# LED_and_LCD.net
KiCad netlist of a schematic drawn in Altium Designer
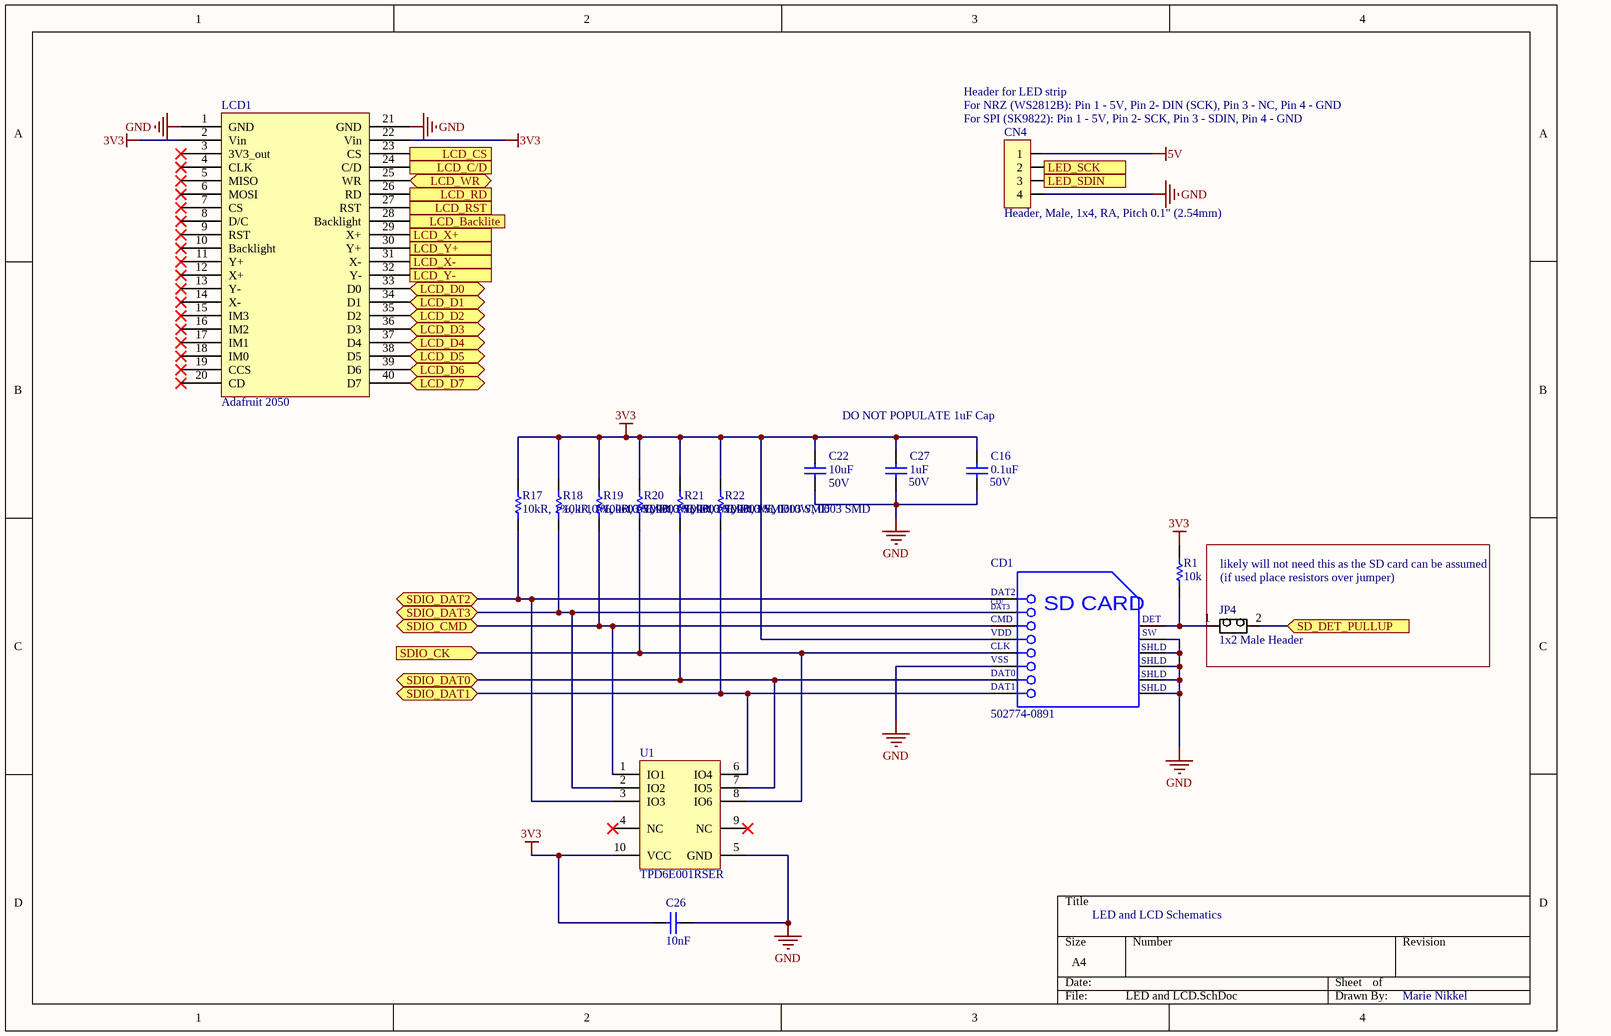
[diagram p0: LED and LCD.SchDoc]

(export (version "E")
  (design (tool "Eeschema 10.0.6"))
  (components
    (comp (ref "C16")
      (value "CL10B104JB8NNNC")
      (footprint "FP-CL10-0_1-IPC_A")
      (description "CAP CER 0.1UF 50V X7R 0603")
      (fields
        (field (name "TOLERANCE") "5%")
        (field (name "VOLTAGE") "50V")
        (field (name "CAPACITANCE") "0.1uF")
      )
      (libsource (lib "AUVIC") (part "CAP-NP-2"))
    )
    (comp (ref "C22")
      (value "CL31B106KBHNNNE")
      (footprint "CAPC3216X180X50ML20T30")
      (description "Cap Ceramic 10uF 50V X7R 10% Pad SMD 1206 125°C T/R")
      (fields
        (field (name "VOLTAGE RATING (DC)") "50V")
        (field (name "CAPACITANCE") "10uF")
        (field (name "TOLERANCE") "10%")
      )
      (libsource (lib "AUVIC") (part "CAP-NP-2"))
    )
    (comp (ref "C26")
      (value "10nF")
      (footprint "CAPC1608N(0603\")")
      (description "Capacitor, Ceramic, 50V, +/- 10%, 0603 SMD")
      (fields
        (field (name "MFG") "Samsung")
        (field (name "Comment") "10 nF, 50V 0603 SMD, Ceramic")
        (field (name "CREATED BY") "Gabriel")
        (field (name "PUBLISHER") "AUVic")
      )
      (libsource (lib "") (part "Symbol_1"))
    )
    (comp (ref "C27")
      (value "CL21B105KBFNNNG")
      (footprint "0803 CAP")
      (description "SAMSUNG ELECTRO-MECHANICS - CL21B105KBFNNNG - MLCC CAPACITORS")
      (fields
        (field (name "CAPACITANCE") "1uF")
        (field (name "TOLERANCE") "10%")
        (field (name "VOLTAGE") "50V")
      )
      (libsource (lib "") (part "Symbol_3"))
    )
    (comp (ref "CD1")
      (value "502774-0891")
      (footprint "MOLX-502774-0891_V")
      (description "Micro SD Memory Card Connector, 0.5 A, 10 V (DC), -25 to 85 degC, 8-Pin SMT, RoHS, Tape and Reel")
      (fields (field (name "MANUFACTURER") "Molex"))
      (libsource (lib "Altium Content Vault") (part "CN-SD-8-2SW-4S_B"))
    )
    (comp (ref "CN4")
      (value "Header, Male, 1x4, RA, Pitch 0.1\" (2.54mm)")
      (footprint "HEADER, MALE, SHROUDED, 4x1, PITCH 0.1\" (2.54mm), RA")
      (description "Connector Header Through Hole, Right Angle 4 position 0.100\" (2.54mm)")
      (fields (field (name "CREATED BY") "Miguel Manguerra"))
      (libsource (lib "") (part "Symbol_2"))
    )
    (comp (ref "JP4")
      (value "1x2 Male Header")
      (footprint "2X1 Males Header")
      (fields (field (name "MADE BY") "Andy Bates"))
      (libsource (lib "AUVIC") (part "1x2 Male Header"))
    )
    (comp (ref "LCD1")
      (value "Adafruit 2050")
      (footprint "LCD_touchscreen_tft")
      (description "3.5\" TFT 320X480 TOUCHSCREEN")
      (libsource (lib "AUVIC") (part "Adafruit 2050"))
    )
    (comp (ref "R1")
      (value "10k")
      (footprint "RESC1608N(0603\")")
      (description "10kR, 1%, 1/10W, 0603 SMD")
      (fields (field (name "MADE BY") "Ashwin Sira"))
      (libsource (lib "AUVIC") (part "Symbol"))
    )
    (comp (ref "R17")
      (value "10kR, 1%, 1/10W, 0603 SMD")
      (footprint "RESC1608N(0603\")")
      (fields (field (name "MADE BY") "Ashwin Sira"))
      (libsource (lib "AUVIC") (part "Symbol"))
    )
    (comp (ref "R18")
      (value "10kR, 1%, 1/10W, 0603 SMD")
      (footprint "RESC1608N(0603\")")
      (fields (field (name "MADE BY") "Ashwin Sira"))
      (libsource (lib "AUVIC") (part "Symbol"))
    )
    (comp (ref "R19")
      (value "10kR, 1%, 1/10W, 0603 SMD")
      (footprint "RESC1608N(0603\")")
      (fields (field (name "MADE BY") "Ashwin Sira"))
      (libsource (lib "AUVIC") (part "Symbol"))
    )
    (comp (ref "R20")
      (value "10kR, 1%, 1/10W, 0603 SMD")
      (footprint "RESC1608N(0603\")")
      (fields (field (name "MADE BY") "Ashwin Sira"))
      (libsource (lib "AUVIC") (part "Symbol"))
    )
    (comp (ref "R21")
      (value "10kR, 1%, 1/10W, 0603 SMD")
      (footprint "RESC1608N(0603\")")
      (fields (field (name "MADE BY") "Ashwin Sira"))
      (libsource (lib "AUVIC") (part "Symbol"))
    )
    (comp (ref "R22")
      (value "10kR, 1%, 1/10W, 0603 SMD")
      (footprint "RESC1608N(0603\")")
      (fields (field (name "MADE BY") "Ashwin Sira"))
      (libsource (lib "AUVIC") (part "Symbol"))
    )
    (comp (ref "U1")
      (value "TPD6E001RSER")
      (footprint "RSE0010A_V")
      (fields (field (name "MANUFACTURER") "Texas Instruments"))
      (libsource (lib "Altium Content Vault") (part "TI-TPD6E001-UQFN_RSE-10"))
    )
  )
  (nets
    (net (code "1") (name "/LCD_Backlite") (class "Default")
      (node (ref "LCD1") (pin "28") (pinfunction "Backlight_28") (pintype "passive"))
    )
    (net (code "2") (name "/LCD_CS") (class "Default")
      (node (ref "LCD1") (pin "23") (pinfunction "CS_23") (pintype "passive"))
    )
    (net (code "3") (name "/LCD_C{slash}D") (class "Default")
      (node (ref "LCD1") (pin "24") (pinfunction "C/D_24") (pintype "passive"))
    )
    (net (code "4") (name "/LCD_D0") (class "Default")
      (node (ref "LCD1") (pin "33") (pinfunction "D0_33") (pintype "passive"))
    )
    (net (code "5") (name "/LCD_D1") (class "Default")
      (node (ref "LCD1") (pin "34") (pinfunction "D1_34") (pintype "passive"))
    )
    (net (code "6") (name "/LCD_D2") (class "Default")
      (node (ref "LCD1") (pin "35") (pinfunction "D2_35") (pintype "passive"))
    )
    (net (code "7") (name "/LCD_D3") (class "Default")
      (node (ref "LCD1") (pin "36") (pinfunction "D3_36") (pintype "passive"))
    )
    (net (code "8") (name "/LCD_D4") (class "Default")
      (node (ref "LCD1") (pin "37") (pinfunction "D4_37") (pintype "passive"))
    )
    (net (code "9") (name "/LCD_D5") (class "Default")
      (node (ref "LCD1") (pin "38") (pinfunction "D5_38") (pintype "passive"))
    )
    (net (code "10") (name "/LCD_D6") (class "Default")
      (node (ref "LCD1") (pin "39") (pinfunction "D6_39") (pintype "passive"))
    )
    (net (code "11") (name "/LCD_D7") (class "Default")
      (node (ref "LCD1") (pin "40") (pinfunction "D7_40") (pintype "passive"))
    )
    (net (code "12") (name "/LCD_RD") (class "Default")
      (node (ref "LCD1") (pin "26") (pinfunction "RD_26") (pintype "passive"))
    )
    (net (code "13") (name "/LCD_RST") (class "Default")
      (node (ref "LCD1") (pin "27") (pinfunction "RST_27") (pintype "passive"))
    )
    (net (code "14") (name "/LCD_WR") (class "Default")
      (node (ref "LCD1") (pin "25") (pinfunction "WR_25") (pintype "passive"))
    )
    (net (code "15") (name "/LCD_X+") (class "Default")
      (node (ref "LCD1") (pin "29") (pinfunction "X+_29") (pintype "passive"))
    )
    (net (code "16") (name "/LCD_X-") (class "Default")
      (node (ref "LCD1") (pin "31") (pinfunction "X-_31") (pintype "passive"))
    )
    (net (code "17") (name "/LCD_Y+") (class "Default")
      (node (ref "LCD1") (pin "30") (pinfunction "Y+_30") (pintype "passive"))
    )
    (net (code "18") (name "/LCD_Y-") (class "Default")
      (node (ref "LCD1") (pin "32") (pinfunction "Y-_32") (pintype "passive"))
    )
    (net (code "19") (name "/LED_SCK") (class "Default")
      (node (ref "CN4") (pin "2") (pinfunction "2_2") (pintype "passive"))
    )
    (net (code "20") (name "/LED_SDIN") (class "Default")
      (node (ref "CN4") (pin "3") (pinfunction "3_3") (pintype "passive"))
    )
    (net (code "21") (name "/SDIO_CK") (class "Default")
      (node (ref "CD1") (pin "5") (pinfunction "CLK_5") (pintype "passive"))
      (node (ref "R20") (pin "1") (pinfunction "1_1") (pintype "passive"))
      (node (ref "U1") (pin "8") (pinfunction "IO6_8") (pintype "passive"))
    )
    (net (code "22") (name "/SDIO_CMD") (class "Default")
      (node (ref "CD1") (pin "3") (pinfunction "CMD_3") (pintype "passive"))
      (node (ref "R19") (pin "1") (pinfunction "1_1") (pintype "passive"))
      (node (ref "U1") (pin "1") (pinfunction "IO1_1") (pintype "passive"))
    )
    (net (code "23") (name "/SDIO_DAT0") (class "Default")
      (node (ref "CD1") (pin "7") (pinfunction "DAT0_7") (pintype "passive"))
      (node (ref "R21") (pin "1") (pinfunction "1_1") (pintype "passive"))
      (node (ref "U1") (pin "7") (pinfunction "IO5_7") (pintype "passive"))
    )
    (net (code "24") (name "/SDIO_DAT1") (class "Default")
      (node (ref "CD1") (pin "8") (pinfunction "DAT1_8") (pintype "passive"))
      (node (ref "R22") (pin "1") (pinfunction "1_1") (pintype "passive"))
      (node (ref "U1") (pin "6") (pinfunction "IO4_6") (pintype "passive"))
    )
    (net (code "25") (name "/SDIO_DAT2") (class "Default")
      (node (ref "CD1") (pin "1") (pinfunction "DAT2_1") (pintype "passive"))
      (node (ref "R17") (pin "1") (pinfunction "1_1") (pintype "passive"))
      (node (ref "U1") (pin "3") (pinfunction "IO3_3") (pintype "passive"))
    )
    (net (code "26") (name "/SDIO_DAT3") (class "Default")
      (node (ref "CD1") (pin "2") (pinfunction "CD/DAT3_2") (pintype "passive"))
      (node (ref "R18") (pin "1") (pinfunction "1_1") (pintype "passive"))
      (node (ref "U1") (pin "2") (pinfunction "IO2_2") (pintype "passive"))
    )
    (net (code "27") (name "/SD_DET_PULLUP") (class "Default")
      (node (ref "JP4") (pin "2") (pinfunction "2_2") (pintype "passive"))
    )
    (net (code "28") (name "3V3") (class "Default")
      (node (ref "C16") (pin "2") (pinfunction "2_2") (pintype "passive"))
      (node (ref "C22") (pin "2") (pinfunction "2_2") (pintype "passive"))
      (node (ref "C26") (pin "1") (pinfunction "Anode_1") (pintype "passive"))
      (node (ref "C27") (pin "2") (pinfunction "2_2") (pintype "passive"))
      (node (ref "CD1") (pin "4") (pinfunction "VDD_4") (pintype "passive"))
      (node (ref "LCD1") (pin "2") (pinfunction "Vin_2") (pintype "passive"))
      (node (ref "LCD1") (pin "22") (pinfunction "Vin_22") (pintype "passive"))
      (node (ref "R1") (pin "2") (pinfunction "2_2") (pintype "passive"))
      (node (ref "R17") (pin "2") (pinfunction "2_2") (pintype "passive"))
      (node (ref "R18") (pin "2") (pinfunction "2_2") (pintype "passive"))
      (node (ref "R19") (pin "2") (pinfunction "2_2") (pintype "passive"))
      (node (ref "R20") (pin "2") (pinfunction "2_2") (pintype "passive"))
      (node (ref "R21") (pin "2") (pinfunction "2_2") (pintype "passive"))
      (node (ref "R22") (pin "2") (pinfunction "2_2") (pintype "passive"))
      (node (ref "U1") (pin "10") (pinfunction "VCC_10") (pintype "power_in"))
    )
    (net (code "29") (name "5V") (class "Default")
      (node (ref "CN4") (pin "1") (pinfunction "1_1") (pintype "passive"))
    )
    (net (code "30") (name "GND") (class "Default")
      (node (ref "C16") (pin "1") (pinfunction "1_1") (pintype "passive"))
      (node (ref "C22") (pin "1") (pinfunction "1_1") (pintype "passive"))
      (node (ref "C26") (pin "2") (pinfunction "Cathode_2") (pintype "passive"))
      (node (ref "C27") (pin "1") (pinfunction "1_1") (pintype "passive"))
      (node (ref "CD1") (pin "10") (pinfunction "SWITCH_10") (pintype "passive"))
      (node (ref "CD1") (pin "11") (pinfunction "SHLD_11") (pintype "passive"))
      (node (ref "CD1") (pin "12") (pinfunction "SHLD_12") (pintype "passive"))
      (node (ref "CD1") (pin "13") (pinfunction "SHLD_13") (pintype "passive"))
      (node (ref "CD1") (pin "14") (pinfunction "SHLD_14") (pintype "passive"))
      (node (ref "CD1") (pin "6") (pinfunction "VSS_6") (pintype "passive"))
      (node (ref "CN4") (pin "4") (pinfunction "4_4") (pintype "passive"))
      (node (ref "LCD1") (pin "1") (pinfunction "GND_1") (pintype "passive"))
      (node (ref "LCD1") (pin "21") (pinfunction "GND_21") (pintype "passive"))
      (node (ref "U1") (pin "5") (pinfunction "GND_5") (pintype "power_in"))
    )
    (net (code "31") (name "Net-(CD1-DETECT)") (class "Default")
      (node (ref "CD1") (pin "9") (pinfunction "DETECT_9") (pintype "passive"))
      (node (ref "JP4") (pin "1") (pinfunction "1_1") (pintype "passive"))
      (node (ref "R1") (pin "1") (pinfunction "1_1") (pintype "passive"))
    )
    (net (code "32") (name "unconnected-(LCD1-3V3_out-Pad3)") (class "Default")
      (node (ref "LCD1") (pin "3") (pinfunction "3V3_out_3") (pintype "passive+no_connect"))
    )
    (net (code "33") (name "unconnected-(LCD1-Backlight-Pad10)") (class "Default")
      (node (ref "LCD1") (pin "10") (pinfunction "Backlight_10") (pintype "passive+no_connect"))
    )
    (net (code "34") (name "unconnected-(LCD1-CCS-Pad19)") (class "Default")
      (node (ref "LCD1") (pin "19") (pinfunction "CCS_19") (pintype "passive+no_connect"))
    )
    (net (code "35") (name "unconnected-(LCD1-CD-Pad20)") (class "Default")
      (node (ref "LCD1") (pin "20") (pinfunction "CD_20") (pintype "passive+no_connect"))
    )
    (net (code "36") (name "unconnected-(LCD1-CLK-Pad4)") (class "Default")
      (node (ref "LCD1") (pin "4") (pinfunction "CLK_4") (pintype "passive+no_connect"))
    )
    (net (code "37") (name "unconnected-(LCD1-CS-Pad7)") (class "Default")
      (node (ref "LCD1") (pin "7") (pinfunction "CS_7") (pintype "passive+no_connect"))
    )
    (net (code "38") (name "unconnected-(LCD1-D{slash}C-Pad8)") (class "Default")
      (node (ref "LCD1") (pin "8") (pinfunction "D/C_8") (pintype "passive+no_connect"))
    )
    (net (code "39") (name "unconnected-(LCD1-IM0-Pad18)") (class "Default")
      (node (ref "LCD1") (pin "18") (pinfunction "IM0_18") (pintype "passive+no_connect"))
    )
    (net (code "40") (name "unconnected-(LCD1-IM1-Pad17)") (class "Default")
      (node (ref "LCD1") (pin "17") (pinfunction "IM1_17") (pintype "passive+no_connect"))
    )
    (net (code "41") (name "unconnected-(LCD1-IM2-Pad16)") (class "Default")
      (node (ref "LCD1") (pin "16") (pinfunction "IM2_16") (pintype "passive+no_connect"))
    )
    (net (code "42") (name "unconnected-(LCD1-IM3-Pad15)") (class "Default")
      (node (ref "LCD1") (pin "15") (pinfunction "IM3_15") (pintype "passive+no_connect"))
    )
    (net (code "43") (name "unconnected-(LCD1-MISO-Pad5)") (class "Default")
      (node (ref "LCD1") (pin "5") (pinfunction "MISO_5") (pintype "passive+no_connect"))
    )
    (net (code "44") (name "unconnected-(LCD1-MOSI-Pad6)") (class "Default")
      (node (ref "LCD1") (pin "6") (pinfunction "MOSI_6") (pintype "passive+no_connect"))
    )
    (net (code "45") (name "unconnected-(LCD1-RST-Pad9)") (class "Default")
      (node (ref "LCD1") (pin "9") (pinfunction "RST_9") (pintype "passive+no_connect"))
    )
    (net (code "46") (name "unconnected-(LCD1-X+-Pad12)") (class "Default")
      (node (ref "LCD1") (pin "12") (pinfunction "X+_12") (pintype "passive+no_connect"))
    )
    (net (code "47") (name "unconnected-(LCD1-X--Pad14)") (class "Default")
      (node (ref "LCD1") (pin "14") (pinfunction "X-_14") (pintype "passive+no_connect"))
    )
    (net (code "48") (name "unconnected-(LCD1-Y+-Pad11)") (class "Default")
      (node (ref "LCD1") (pin "11") (pinfunction "Y+_11") (pintype "passive+no_connect"))
    )
    (net (code "49") (name "unconnected-(LCD1-Y--Pad13)") (class "Default")
      (node (ref "LCD1") (pin "13") (pinfunction "Y-_13") (pintype "passive+no_connect"))
    )
    (net (code "50") (name "unconnected-(U1-NC-Pad4)") (class "Default")
      (node (ref "U1") (pin "4") (pinfunction "NC_4") (pintype "passive+no_connect"))
    )
    (net (code "51") (name "unconnected-(U1-NC-Pad9)") (class "Default")
      (node (ref "U1") (pin "9") (pinfunction "NC_9") (pintype "passive+no_connect"))
    )
  )
)
